# DC-DC_TPS564208DDCT.net
KiCad netlist of a schematic drawn in Altium Designer
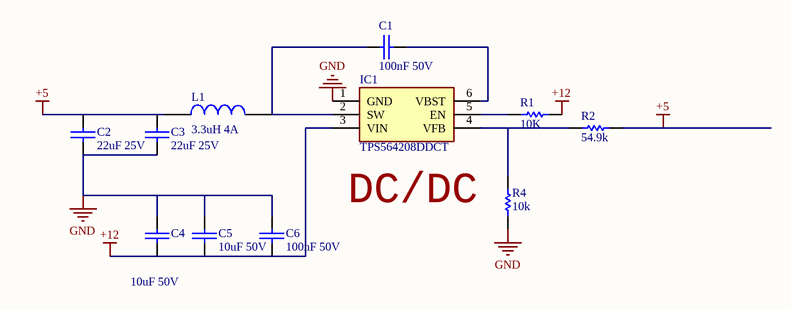
[diagram p0: DC-DC TPS564208DDCT.SchDoc]

(export (version "E")
  (design (tool "Eeschema 10.0.6"))
  (components
    (comp (ref "C1") (value "100nF 50V") (footprint "0402C") (libsource (lib "电容") (part "CAP-NP")))
    (comp (ref "C2")
      (value "22uF 25V")
      (footprint "Capacitance:0805C")
      (libsource (lib "电容") (part "CAP-NP"))
    )
    (comp (ref "C3")
      (value "22uF 25V")
      (footprint "Capacitance:0805C")
      (libsource (lib "电容") (part "CAP-NP"))
    )
    (comp (ref "C4")
      (value "10uF 50V")
      (footprint "Capacitance:0805C")
      (libsource (lib "电容") (part "CAP-NP"))
    )
    (comp (ref "C5")
      (value "10uF 50V")
      (footprint "Capacitance:0805C")
      (libsource (lib "电容") (part "CAP-NP"))
    )
    (comp (ref "C6") (value "100nF 50V") (footprint "0402C") (libsource (lib "电容") (part "CAP-NP")))
    (comp (ref "IC1")
      (value "TPS564208DDCT")
      (footprint "SamacSys:SOT95P280X110-6N")
      (description "Integrated Circuit")
      (fields
        (field (name "MOUSER PART NUMBER") "595-TPS564208DDCT")
        (field (name "RS PART NUMBER") "1330753P")
        (field (name "COMPONENTLINK2URL") "file:///C:/Users/58218/Downloads/C486062_TPS564208DDCR_2020-01-18%20(1).PDF")
      )
      (libsource (lib "*") (part "TPS564208DDCT"))
    )
    (comp (ref "L1")
      (value "3.3uH 4A")
      (footprint "Inductance:SMD4.3*4*2")
      (description "CMLF0504-3R3MTT")
      (libsource (lib "电感") (part "INDUCTOR"))
    )
    (comp (ref "R1") (value "10K") (footprint "0402R") (libsource (lib "电阻") (part "RES")))
    (comp (ref "R2") (value "54.9k") (footprint "0402R") (libsource (lib "电阻") (part "RES")))
    (comp (ref "R4") (value "10k") (footprint "0402R") (libsource (lib "电阻") (part "RES")))
  )
  (nets
    (net (code "1") (name "+5") (class "Default")
      (node (ref "C2") (pin "2") (pinfunction "2_2") (pintype "passive"))
      (node (ref "C3") (pin "2") (pinfunction "2_2") (pintype "passive"))
      (node (ref "L1") (pin "1") (pinfunction "1_1") (pintype "passive"))
      (node (ref "R2") (pin "2") (pinfunction "2_2") (pintype "passive"))
    )
    (net (code "2") (name "+12") (class "Default")
      (node (ref "C4") (pin "1") (pinfunction "1_1") (pintype "passive"))
      (node (ref "C5") (pin "1") (pinfunction "1_1") (pintype "passive"))
      (node (ref "C6") (pin "1") (pinfunction "1_1") (pintype "passive"))
      (node (ref "IC1") (pin "3") (pinfunction "VIN_3") (pintype "passive"))
      (node (ref "R1") (pin "2") (pinfunction "2_2") (pintype "passive"))
    )
    (net (code "3") (name "GND") (class "Default")
      (node (ref "C2") (pin "1") (pinfunction "1_1") (pintype "passive"))
      (node (ref "C3") (pin "1") (pinfunction "1_1") (pintype "passive"))
      (node (ref "C4") (pin "2") (pinfunction "2_2") (pintype "passive"))
      (node (ref "C5") (pin "2") (pinfunction "2_2") (pintype "passive"))
      (node (ref "C6") (pin "2") (pinfunction "2_2") (pintype "passive"))
      (node (ref "IC1") (pin "1") (pinfunction "GND_1") (pintype "passive"))
      (node (ref "R4") (pin "1") (pinfunction "1_1") (pintype "passive"))
    )
    (net (code "4") (name "Net-(IC1-EN)") (class "Default")
      (node (ref "IC1") (pin "5") (pinfunction "EN_5") (pintype "passive"))
      (node (ref "R1") (pin "1") (pinfunction "1_1") (pintype "passive"))
    )
    (net (code "5") (name "Net-(IC1-SW)") (class "Default")
      (node (ref "C1") (pin "1") (pinfunction "1_1") (pintype "passive"))
      (node (ref "IC1") (pin "2") (pinfunction "SW_2") (pintype "passive"))
      (node (ref "L1") (pin "2") (pinfunction "2_2") (pintype "passive"))
    )
    (net (code "6") (name "Net-(IC1-VBST)") (class "Default")
      (node (ref "C1") (pin "2") (pinfunction "2_2") (pintype "passive"))
      (node (ref "IC1") (pin "6") (pinfunction "VBST_6") (pintype "passive"))
    )
    (net (code "7") (name "Net-(IC1-VFB)") (class "Default")
      (node (ref "IC1") (pin "4") (pinfunction "VFB_4") (pintype "passive"))
      (node (ref "R2") (pin "1") (pinfunction "1_1") (pintype "passive"))
      (node (ref "R4") (pin "2") (pinfunction "2_2") (pintype "passive"))
    )
  )
)
